# power.net
KiCad netlist of a schematic drawn in Altium Designer
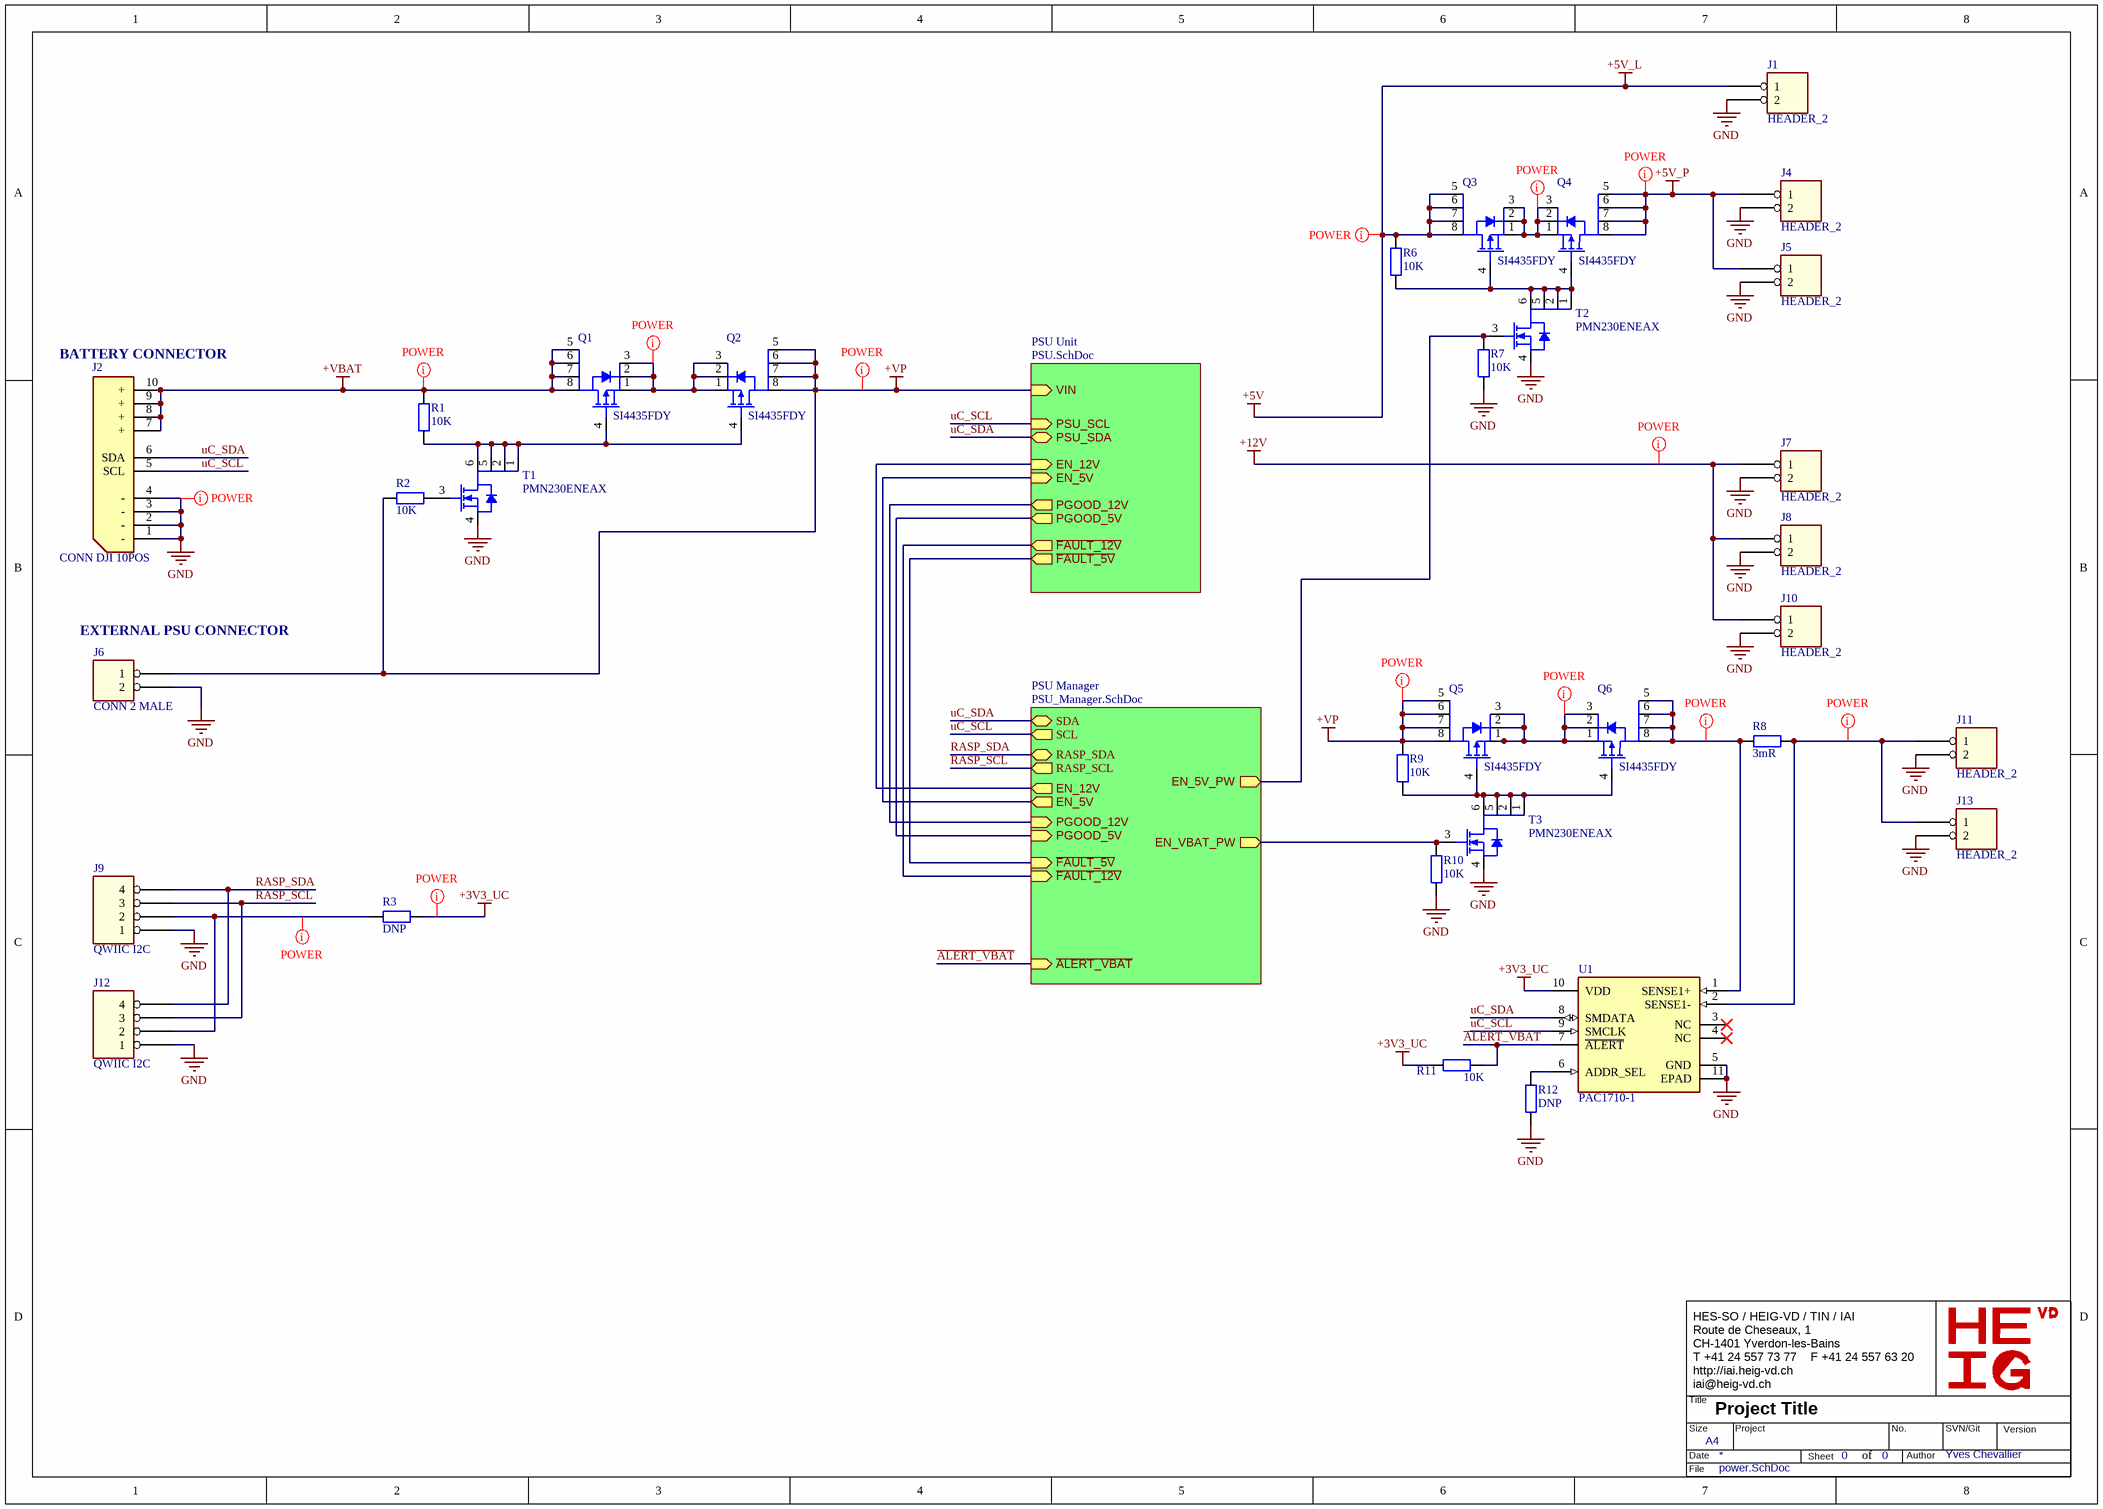
[diagram p0: power.SchDoc]

(export (version "E")
  (design (tool "Eeschema 10.0.6"))
  (components
    (comp (ref "J1")
      (value "HEADER_2")
      (footprint "PHOENIX MKDS 5/2-6,35 - 1714955")
      (libsource (lib "Battery_PSU") (part "HEADER_2"))
    )
    (comp (ref "J2")
      (value "CONN DJI 10POS")
      (footprint "DJI Battery Connector")
      (libsource (lib "Battery_PSU") (part "CONN DJI 10POS"))
    )
    (comp (ref "J4")
      (value "HEADER_2")
      (footprint "PHOENIX MKDS 5/2-6,35 - 1714955")
      (libsource (lib "Battery_PSU") (part "HEADER_2"))
    )
    (comp (ref "J5")
      (value "HEADER_2")
      (footprint "PHOENIX MKDS 5/2-6,35 - 1714955")
      (libsource (lib "Battery_PSU") (part "HEADER_2"))
    )
    (comp (ref "J6")
      (value "CONN 2 MALE")
      (footprint "PHOENIX MKDS 5/2-6,35 - 1714955")
      (libsource (lib "Battery_PSU") (part "CONN 2 MALE"))
    )
    (comp (ref "J7")
      (value "HEADER_2")
      (footprint "PHOENIX MKDS 5/2-6,35 - 1714955")
      (libsource (lib "Battery_PSU") (part "HEADER_2"))
    )
    (comp (ref "J8")
      (value "HEADER_2")
      (footprint "PHOENIX MKDS 5/2-6,35 - 1714955")
      (libsource (lib "Battery_PSU") (part "HEADER_2"))
    )
    (comp (ref "J9")
      (value "QWIIC I2C")
      (footprint "JST_SM04B-SRSS-TB(LF)(SN)")
      (fields (field (name "MANUFACTURER") "SparkFun Electronics"))
      (libsource (lib "Battery_PSU") (part "QWIIC I2C"))
    )
    (comp (ref "J10")
      (value "HEADER_2")
      (footprint "PHOENIX MKDS 5/2-6,35 - 1714955")
      (libsource (lib "Battery_PSU") (part "HEADER_2"))
    )
    (comp (ref "J11")
      (value "HEADER_2")
      (footprint "PHOENIX MKDS 5/2-6,35 - 1714955")
      (libsource (lib "Battery_PSU") (part "HEADER_2"))
    )
    (comp (ref "J12")
      (value "QWIIC I2C")
      (footprint "JST_SM04B-SRSS-TB(LF)(SN)")
      (fields (field (name "MANUFACTURER") "SparkFun Electronics"))
      (libsource (lib "Battery_PSU") (part "QWIIC I2C"))
    )
    (comp (ref "J13")
      (value "HEADER_2")
      (footprint "PHOENIX MKDS 5/2-6,35 - 1714955")
      (libsource (lib "Battery_PSU") (part "HEADER_2"))
    )
    (comp (ref "Q1")
      (value "SI4435FDY")
      (footprint "SOIC-8 - N")
      (description "MOSFET P-CH 30V 12.6A 8SOIC")
      (libsource (lib "Battery_PSU") (part "MOSFET P-CH 30V 12.6A 8SOIC"))
    )
    (comp (ref "Q2")
      (value "SI4435FDY")
      (footprint "SOIC-8 - N")
      (description "MOSFET P-CH 30V 12.6A 8SOIC")
      (libsource (lib "Battery_PSU") (part "MOSFET P-CH 30V 12.6A 8SOIC"))
    )
    (comp (ref "Q3")
      (value "SI4435FDY")
      (footprint "SOIC-8 - N")
      (description "MOSFET P-CH 30V 12.6A 8SOIC")
      (libsource (lib "Battery_PSU") (part "MOSFET P-CH 30V 12.6A 8SOIC"))
    )
    (comp (ref "Q4")
      (value "SI4435FDY")
      (footprint "SOIC-8 - N")
      (description "MOSFET P-CH 30V 12.6A 8SOIC")
      (libsource (lib "Battery_PSU") (part "MOSFET P-CH 30V 12.6A 8SOIC"))
    )
    (comp (ref "Q5")
      (value "SI4435FDY")
      (footprint "SOIC-8 - N")
      (description "MOSFET P-CH 30V 12.6A 8SOIC")
      (libsource (lib "Battery_PSU") (part "MOSFET P-CH 30V 12.6A 8SOIC"))
    )
    (comp (ref "Q6")
      (value "SI4435FDY")
      (footprint "SOIC-8 - N")
      (description "MOSFET P-CH 30V 12.6A 8SOIC")
      (libsource (lib "Battery_PSU") (part "MOSFET P-CH 30V 12.6A 8SOIC"))
    )
    (comp (ref "R1")
      (value "10K")
      (footprint "SM/R_0603")
      (description "Résistance 0603 100mW 1% 10K")
      (fields (field (name "MANUFACTURER") "Yageo") (field (name "POWER") "100mW"))
      (libsource (lib "Battery_PSU") (part "RES SMD 10K OHM 1% 1/10W 0603"))
    )
    (comp (ref "R2")
      (value "10K")
      (footprint "SM/R_0603")
      (description "Résistance 0603 100mW 1% 10K")
      (fields (field (name "MANUFACTURER") "Yageo") (field (name "POWER") "100mW"))
      (libsource (lib "Battery_PSU") (part "RES SMD 10K OHM 1% 1/10W 0603"))
    )
    (comp (ref "R3")
      (value "DNP")
      (footprint "SM/R_0603")
      (description "RES SMD DNP JUMPER 1/10W 0603")
      (libsource (lib "Battery_PSU") (part "RES SMD DNP JUMPER 1/10W 0603"))
    )
    (comp (ref "R6")
      (value "10K")
      (footprint "SM/R_0603")
      (description "Résistance 0603 100mW 1% 10K")
      (fields (field (name "MANUFACTURER") "Yageo") (field (name "POWER") "100mW"))
      (libsource (lib "Battery_PSU") (part "RES SMD 10K OHM 1% 1/10W 0603"))
    )
    (comp (ref "R7")
      (value "10K")
      (footprint "SM/R_0603")
      (description "Résistance 0603 100mW 1% 10K")
      (fields (field (name "MANUFACTURER") "Yageo") (field (name "POWER") "100mW"))
      (libsource (lib "Battery_PSU") (part "RES SMD 10K OHM 1% 1/10W 0603"))
    )
    (comp (ref "R8")
      (value "3mR")
      (footprint "SM/R_1210")
      (description "RES 0.003 OHM 5% 1W 1210")
      (fields (field (name "MANUFACTURER") "Rohm") (field (name "POWER") "1W"))
      (libsource (lib "Battery_PSU") (part "RES 0.003 OHM 5% 1W 1210"))
    )
    (comp (ref "R9")
      (value "10K")
      (footprint "SM/R_0603")
      (description "Résistance 0603 100mW 1% 10K")
      (fields (field (name "MANUFACTURER") "Yageo") (field (name "POWER") "100mW"))
      (libsource (lib "Battery_PSU") (part "RES SMD 10K OHM 1% 1/10W 0603"))
    )
    (comp (ref "R10")
      (value "10K")
      (footprint "SM/R_0603")
      (description "Résistance 0603 100mW 1% 10K")
      (fields (field (name "MANUFACTURER") "Yageo") (field (name "POWER") "100mW"))
      (libsource (lib "Battery_PSU") (part "RES SMD 10K OHM 1% 1/10W 0603"))
    )
    (comp (ref "R11")
      (value "10K")
      (footprint "SM/R_0603")
      (description "Résistance 0603 100mW 1% 10K")
      (fields (field (name "MANUFACTURER") "Yageo") (field (name "POWER") "100mW"))
      (libsource (lib "Battery_PSU") (part "RES SMD 10K OHM 1% 1/10W 0603"))
    )
    (comp (ref "R12")
      (value "DNP")
      (footprint "SM/R_0603")
      (description "RES SMD DNP JUMPER 1/10W 0603")
      (libsource (lib "Battery_PSU") (part "RES SMD DNP JUMPER 1/10W 0603"))
    )
    (comp (ref "T1")
      (value "PMN230ENEAX")
      (footprint "TSOP-6")
      (description "MOSFET N-CH 60V 1.8A 6TSOP")
      (libsource (lib "Battery_PSU") (part "MOSFET N-CH 60V 1.8A 6TSOP"))
    )
    (comp (ref "T2")
      (value "PMN230ENEAX")
      (footprint "TSOP-6")
      (description "MOSFET N-CH 60V 1.8A 6TSOP")
      (libsource (lib "Battery_PSU") (part "MOSFET N-CH 60V 1.8A 6TSOP"))
    )
    (comp (ref "T3")
      (value "PMN230ENEAX")
      (footprint "TSOP-6")
      (description "MOSFET N-CH 60V 1.8A 6TSOP")
      (libsource (lib "Battery_PSU") (part "MOSFET N-CH 60V 1.8A 6TSOP"))
    )
    (comp (ref "U1")
      (value "PAC1710-1")
      (footprint "WFDFN-10")
      (description "IC CURRENT SENSE MON SGL 10VDFN")
      (fields (field (name "MANUFACTURER") "Microchip"))
      (libsource (lib "Battery_PSU") (part "IC CURRENT SENSE MON SGL 10VDFN"))
    )
  )
  (nets
    (net (code "1") (name "+3V3_UC") (class "Default")
      (node (ref "R11") (pin "1") (pinfunction "1_1") (pintype "passive"))
      (node (ref "R3") (pin "1") (pinfunction "1_1") (pintype "passive"))
      (node (ref "U1") (pin "10") (pinfunction "VDD_10") (pintype "power_in"))
    )
    (net (code "2") (name "+5V") (class "Default")
      (node (ref "J1") (pin "1") (pinfunction "1_1") (pintype "passive"))
      (node (ref "Q3") (pin "5") (pinfunction "D_5") (pintype "passive"))
      (node (ref "Q3") (pin "6") (pinfunction "D_6") (pintype "passive"))
      (node (ref "Q3") (pin "7") (pinfunction "D_7") (pintype "passive"))
      (node (ref "Q3") (pin "8") (pinfunction "D_8") (pintype "passive"))
      (node (ref "R6") (pin "1") (pinfunction "1_1") (pintype "passive"))
    )
    (net (code "3") (name "+5V_P") (class "Default")
      (node (ref "J4") (pin "1") (pinfunction "1_1") (pintype "passive"))
      (node (ref "J5") (pin "1") (pinfunction "1_1") (pintype "passive"))
      (node (ref "Q4") (pin "5") (pinfunction "D_5") (pintype "passive"))
      (node (ref "Q4") (pin "6") (pinfunction "D_6") (pintype "passive"))
      (node (ref "Q4") (pin "7") (pinfunction "D_7") (pintype "passive"))
      (node (ref "Q4") (pin "8") (pinfunction "D_8") (pintype "passive"))
    )
    (net (code "4") (name "+12V") (class "Default")
      (node (ref "J10") (pin "1") (pinfunction "1_1") (pintype "passive"))
      (node (ref "J7") (pin "1") (pinfunction "1_1") (pintype "passive"))
      (node (ref "J8") (pin "1") (pinfunction "1_1") (pintype "passive"))
    )
    (net (code "5") (name "+VBAT") (class "Default")
      (node (ref "J2") (pin "10") (pinfunction "+_10") (pintype "power_in"))
      (node (ref "J2") (pin "7") (pinfunction "+_7") (pintype "power_in"))
      (node (ref "J2") (pin "8") (pinfunction "+_8") (pintype "power_in"))
      (node (ref "J2") (pin "9") (pinfunction "+_9") (pintype "power_in"))
      (node (ref "Q1") (pin "5") (pinfunction "D_5") (pintype "passive"))
      (node (ref "Q1") (pin "6") (pinfunction "D_6") (pintype "passive"))
      (node (ref "Q1") (pin "7") (pinfunction "D_7") (pintype "passive"))
      (node (ref "Q1") (pin "8") (pinfunction "D_8") (pintype "passive"))
      (node (ref "R1") (pin "1") (pinfunction "1_1") (pintype "passive"))
    )
    (net (code "6") (name "+VP") (class "Default")
      (node (ref "J6") (pin "1") (pinfunction "1_1") (pintype "passive"))
      (node (ref "Q2") (pin "5") (pinfunction "D_5") (pintype "passive"))
      (node (ref "Q2") (pin "6") (pinfunction "D_6") (pintype "passive"))
      (node (ref "Q2") (pin "7") (pinfunction "D_7") (pintype "passive"))
      (node (ref "Q2") (pin "8") (pinfunction "D_8") (pintype "passive"))
      (node (ref "Q5") (pin "5") (pinfunction "D_5") (pintype "passive"))
      (node (ref "Q5") (pin "6") (pinfunction "D_6") (pintype "passive"))
      (node (ref "Q5") (pin "7") (pinfunction "D_7") (pintype "passive"))
      (node (ref "Q5") (pin "8") (pinfunction "D_8") (pintype "passive"))
      (node (ref "R2") (pin "1") (pinfunction "1_1") (pintype "passive"))
      (node (ref "R9") (pin "1") (pinfunction "1_1") (pintype "passive"))
    )
    (net (code "7") (name "/ALERT_VBAT") (class "Default")
      (node (ref "R11") (pin "2") (pinfunction "2_2") (pintype "passive"))
      (node (ref "U1") (pin "7") (pinfunction "ALERT_7") (pintype "open_collector"))
    )
    (net (code "9") (name "/EN_5V_PW") (class "Default")
      (node (ref "R7") (pin "2") (pinfunction "2_2") (pintype "passive"))
      (node (ref "T2") (pin "3") (pinfunction "G_3") (pintype "passive"))
    )
    (net (code "11") (name "/EN_VBAT_PW") (class "Default")
      (node (ref "R10") (pin "2") (pinfunction "2_2") (pintype "passive"))
      (node (ref "T3") (pin "3") (pinfunction "G_3") (pintype "passive"))
    )
    (net (code "16") (name "/RASP_SCL") (class "Default")
      (node (ref "J12") (pin "3") (pinfunction "3_3") (pintype "passive"))
      (node (ref "J9") (pin "3") (pinfunction "3_3") (pintype "passive"))
    )
    (net (code "17") (name "/RASP_SDA") (class "Default")
      (node (ref "J12") (pin "4") (pinfunction "4_4") (pintype "passive"))
      (node (ref "J9") (pin "4") (pinfunction "4_4") (pintype "passive"))
    )
    (net (code "18") (name "/uC_SCL") (class "Default")
      (node (ref "J2") (pin "5") (pinfunction "SCL_5") (pintype "passive"))
      (node (ref "U1") (pin "9") (pinfunction "SMCLK_9") (pintype "input"))
    )
    (net (code "19") (name "/uC_SDA") (class "Default")
      (node (ref "J2") (pin "6") (pinfunction "SDA_6") (pintype "passive"))
      (node (ref "U1") (pin "8") (pinfunction "SMDATA_8") (pintype "bidirectional"))
    )
    (net (code "20") (name "GND") (class "Default")
      (node (ref "J1") (pin "2") (pinfunction "2_2") (pintype "passive"))
      (node (ref "J10") (pin "2") (pinfunction "2_2") (pintype "passive"))
      (node (ref "J11") (pin "2") (pinfunction "2_2") (pintype "passive"))
      (node (ref "J12") (pin "1") (pinfunction "1_1") (pintype "passive"))
      (node (ref "J13") (pin "2") (pinfunction "2_2") (pintype "passive"))
      (node (ref "J2") (pin "1") (pinfunction "-_1") (pintype "power_in"))
      (node (ref "J2") (pin "2") (pinfunction "-_2") (pintype "power_in"))
      (node (ref "J2") (pin "3") (pinfunction "-_3") (pintype "power_in"))
      (node (ref "J2") (pin "4") (pinfunction "-_4") (pintype "power_in"))
      (node (ref "J4") (pin "2") (pinfunction "2_2") (pintype "passive"))
      (node (ref "J5") (pin "2") (pinfunction "2_2") (pintype "passive"))
      (node (ref "J6") (pin "2") (pinfunction "2_2") (pintype "passive"))
      (node (ref "J7") (pin "2") (pinfunction "2_2") (pintype "passive"))
      (node (ref "J8") (pin "2") (pinfunction "2_2") (pintype "passive"))
      (node (ref "J9") (pin "1") (pinfunction "1_1") (pintype "passive"))
      (node (ref "R10") (pin "1") (pinfunction "1_1") (pintype "passive"))
      (node (ref "R12") (pin "2") (pinfunction "2_2") (pintype "passive"))
      (node (ref "R7") (pin "1") (pinfunction "1_1") (pintype "passive"))
      (node (ref "T1") (pin "4") (pinfunction "S_4") (pintype "passive"))
      (node (ref "T2") (pin "4") (pinfunction "S_4") (pintype "passive"))
      (node (ref "T3") (pin "4") (pinfunction "S_4") (pintype "passive"))
      (node (ref "U1") (pin "11") (pinfunction "EPAD_11") (pintype "passive"))
      (node (ref "U1") (pin "5") (pinfunction "GND_5") (pintype "power_in"))
    )
    (net (code "21") (name "Net-(J12-Pad2)") (class "Default")
      (node (ref "J12") (pin "2") (pinfunction "2_2") (pintype "passive"))
      (node (ref "J9") (pin "2") (pinfunction "2_2") (pintype "passive"))
      (node (ref "R3") (pin "2") (pinfunction "2_2") (pintype "passive"))
    )
    (net (code "22") (name "Net-(Q1-G)") (class "Default")
      (node (ref "Q1") (pin "4") (pinfunction "G_4") (pintype "passive"))
      (node (ref "Q2") (pin "4") (pinfunction "G_4") (pintype "passive"))
      (node (ref "R1") (pin "2") (pinfunction "2_2") (pintype "passive"))
      (node (ref "T1") (pin "1") (pinfunction "D_1") (pintype "passive"))
      (node (ref "T1") (pin "2") (pinfunction "D_2") (pintype "passive"))
      (node (ref "T1") (pin "5") (pinfunction "D_5") (pintype "passive"))
      (node (ref "T1") (pin "6") (pinfunction "D_6") (pintype "passive"))
    )
    (net (code "23") (name "Net-(Q1-S-Pad1)") (class "Default")
      (node (ref "Q1") (pin "1") (pinfunction "S_1") (pintype "passive"))
      (node (ref "Q1") (pin "2") (pinfunction "S_2") (pintype "passive"))
      (node (ref "Q1") (pin "3") (pinfunction "S_3") (pintype "passive"))
      (node (ref "Q2") (pin "1") (pinfunction "S_1") (pintype "passive"))
      (node (ref "Q2") (pin "2") (pinfunction "S_2") (pintype "passive"))
      (node (ref "Q2") (pin "3") (pinfunction "S_3") (pintype "passive"))
    )
    (net (code "24") (name "Net-(Q3-G)") (class "Default")
      (node (ref "Q3") (pin "4") (pinfunction "G_4") (pintype "passive"))
      (node (ref "Q4") (pin "4") (pinfunction "G_4") (pintype "passive"))
      (node (ref "R6") (pin "2") (pinfunction "2_2") (pintype "passive"))
      (node (ref "T2") (pin "1") (pinfunction "D_1") (pintype "passive"))
      (node (ref "T2") (pin "2") (pinfunction "D_2") (pintype "passive"))
      (node (ref "T2") (pin "5") (pinfunction "D_5") (pintype "passive"))
      (node (ref "T2") (pin "6") (pinfunction "D_6") (pintype "passive"))
    )
    (net (code "25") (name "Net-(Q3-S-Pad1)") (class "Default")
      (node (ref "Q3") (pin "1") (pinfunction "S_1") (pintype "passive"))
      (node (ref "Q3") (pin "2") (pinfunction "S_2") (pintype "passive"))
      (node (ref "Q3") (pin "3") (pinfunction "S_3") (pintype "passive"))
      (node (ref "Q4") (pin "1") (pinfunction "S_1") (pintype "passive"))
      (node (ref "Q4") (pin "2") (pinfunction "S_2") (pintype "passive"))
      (node (ref "Q4") (pin "3") (pinfunction "S_3") (pintype "passive"))
    )
    (net (code "26") (name "Net-(Q5-G)") (class "Default")
      (node (ref "Q5") (pin "4") (pinfunction "G_4") (pintype "passive"))
      (node (ref "Q6") (pin "4") (pinfunction "G_4") (pintype "passive"))
      (node (ref "R9") (pin "2") (pinfunction "2_2") (pintype "passive"))
      (node (ref "T3") (pin "1") (pinfunction "D_1") (pintype "passive"))
      (node (ref "T3") (pin "2") (pinfunction "D_2") (pintype "passive"))
      (node (ref "T3") (pin "5") (pinfunction "D_5") (pintype "passive"))
      (node (ref "T3") (pin "6") (pinfunction "D_6") (pintype "passive"))
    )
    (net (code "27") (name "Net-(Q5-S-Pad1)") (class "Default")
      (node (ref "Q5") (pin "1") (pinfunction "S_1") (pintype "passive"))
      (node (ref "Q5") (pin "2") (pinfunction "S_2") (pintype "passive"))
      (node (ref "Q5") (pin "3") (pinfunction "S_3") (pintype "passive"))
      (node (ref "Q6") (pin "1") (pinfunction "S_1") (pintype "passive"))
      (node (ref "Q6") (pin "2") (pinfunction "S_2") (pintype "passive"))
      (node (ref "Q6") (pin "3") (pinfunction "S_3") (pintype "passive"))
    )
    (net (code "28") (name "Net-(T1-G)") (class "Default")
      (node (ref "R2") (pin "2") (pinfunction "2_2") (pintype "passive"))
      (node (ref "T1") (pin "3") (pinfunction "G_3") (pintype "passive"))
    )
    (net (code "29") (name "Net-(U1-ADDR_SEL)") (class "Default")
      (node (ref "R12") (pin "1") (pinfunction "1_1") (pintype "passive"))
      (node (ref "U1") (pin "6") (pinfunction "ADDR_SEL_6") (pintype "input"))
    )
    (net (code "30") (name "Net-(U1-SENSE1+)") (class "Default")
      (node (ref "Q6") (pin "5") (pinfunction "D_5") (pintype "passive"))
      (node (ref "Q6") (pin "6") (pinfunction "D_6") (pintype "passive"))
      (node (ref "Q6") (pin "7") (pinfunction "D_7") (pintype "passive"))
      (node (ref "Q6") (pin "8") (pinfunction "D_8") (pintype "passive"))
      (node (ref "R8") (pin "1") (pinfunction "1_1") (pintype "passive"))
      (node (ref "U1") (pin "1") (pinfunction "SENSE1+_1") (pintype "input"))
    )
    (net (code "31") (name "Net-(U1-SENSE1-)") (class "Default")
      (node (ref "J11") (pin "1") (pinfunction "1_1") (pintype "passive"))
      (node (ref "J13") (pin "1") (pinfunction "1_1") (pintype "passive"))
      (node (ref "R8") (pin "2") (pinfunction "2_2") (pintype "passive"))
      (node (ref "U1") (pin "2") (pinfunction "SENSE1-_2") (pintype "input"))
    )
    (net (code "32") (name "unconnected-(U1-NC-Pad3)") (class "Default")
      (node (ref "U1") (pin "3") (pinfunction "NC_3") (pintype "passive+no_connect"))
    )
    (net (code "33") (name "unconnected-(U1-NC-Pad4)") (class "Default")
      (node (ref "U1") (pin "4") (pinfunction "NC_4") (pintype "passive+no_connect"))
    )
  )
)
